# AT1846S.net
KiCad netlist of a schematic drawn in EAGLE
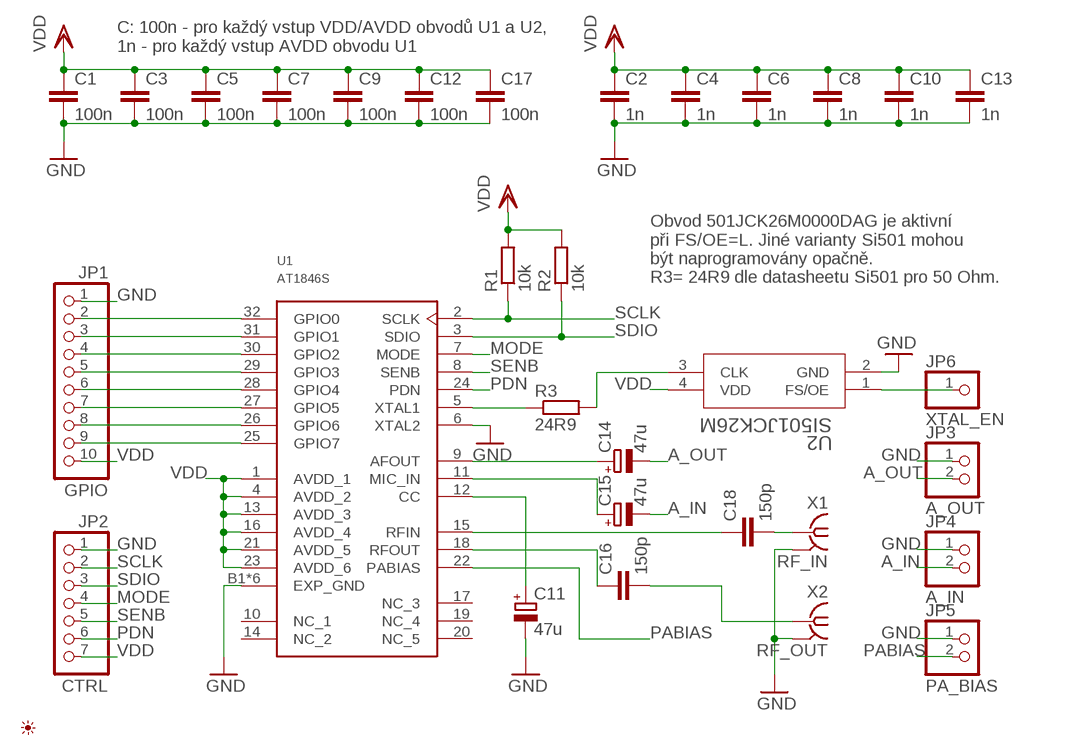
[diagram p0: schematic, sheet 1]

(export (version "E")
  (design (tool "Eeschema 10.0.6"))
  (components
    (comp (ref "C1")
      (value "100n")
      (footprint "eagle-import:C0603")
      (libsource (lib "eagle-import") (part "C-EUC0603"))
    )
    (comp (ref "C2")
      (value "1n")
      (footprint "eagle-import:C0603")
      (libsource (lib "eagle-import") (part "C-EUC0603"))
    )
    (comp (ref "C3")
      (value "100n")
      (footprint "eagle-import:C0603")
      (libsource (lib "eagle-import") (part "C-EUC0603"))
    )
    (comp (ref "C4")
      (value "1n")
      (footprint "eagle-import:C0603")
      (libsource (lib "eagle-import") (part "C-EUC0603"))
    )
    (comp (ref "C5")
      (value "100n")
      (footprint "eagle-import:C0603")
      (libsource (lib "eagle-import") (part "C-EUC0603"))
    )
    (comp (ref "C6")
      (value "1n")
      (footprint "eagle-import:C0603")
      (libsource (lib "eagle-import") (part "C-EUC0603"))
    )
    (comp (ref "C7")
      (value "100n")
      (footprint "eagle-import:C0603")
      (libsource (lib "eagle-import") (part "C-EUC0603"))
    )
    (comp (ref "C8")
      (value "1n")
      (footprint "eagle-import:C0603")
      (libsource (lib "eagle-import") (part "C-EUC0603"))
    )
    (comp (ref "C9")
      (value "100n")
      (footprint "eagle-import:C0603")
      (libsource (lib "eagle-import") (part "C-EUC0603"))
    )
    (comp (ref "C10")
      (value "1n")
      (footprint "eagle-import:C0603")
      (libsource (lib "eagle-import") (part "C-EUC0603"))
    )
    (comp (ref "C11")
      (value "47u")
      (footprint "eagle-import:SMC_A")
      (libsource (lib "eagle-import") (part "CPOL-EUSMCA"))
    )
    (comp (ref "C12")
      (value "100n")
      (footprint "eagle-import:C0603")
      (libsource (lib "eagle-import") (part "C-EUC0603"))
    )
    (comp (ref "C13")
      (value "1n")
      (footprint "eagle-import:C0603")
      (libsource (lib "eagle-import") (part "C-EUC0603"))
    )
    (comp (ref "C14")
      (value "47u")
      (footprint "eagle-import:SMC_A")
      (libsource (lib "eagle-import") (part "CPOL-EUSMCA"))
    )
    (comp (ref "C15")
      (value "47u")
      (footprint "eagle-import:SMC_A")
      (libsource (lib "eagle-import") (part "CPOL-EUSMCA"))
    )
    (comp (ref "C16")
      (value "150p")
      (footprint "eagle-import:C0603")
      (libsource (lib "eagle-import") (part "C-EUC0603"))
    )
    (comp (ref "C17")
      (value "100n")
      (footprint "eagle-import:C0603")
      (libsource (lib "eagle-import") (part "C-EUC0603"))
    )
    (comp (ref "C18")
      (value "150p")
      (footprint "eagle-import:C0603")
      (libsource (lib "eagle-import") (part "C-EUC0603"))
    )
    (comp (ref "JP1")
      (value "GPIO")
      (footprint "eagle-import:1X10")
      (libsource (lib "eagle-import") (part "PINHD-1X10"))
    )
    (comp (ref "JP2")
      (value "CTRL")
      (footprint "eagle-import:1X07")
      (libsource (lib "eagle-import") (part "PINHD-1X7"))
    )
    (comp (ref "JP3")
      (value "A_OUT")
      (footprint "eagle-import:1X02")
      (libsource (lib "eagle-import") (part "PINHD-1X2"))
    )
    (comp (ref "JP4")
      (value "A_IN")
      (footprint "eagle-import:1X02")
      (libsource (lib "eagle-import") (part "PINHD-1X2"))
    )
    (comp (ref "JP5")
      (value "PA_BIAS")
      (footprint "eagle-import:1X02")
      (libsource (lib "eagle-import") (part "PINHD-1X2"))
    )
    (comp (ref "JP6")
      (value "XTAL_EN")
      (footprint "eagle-import:1X01")
      (libsource (lib "eagle-import") (part "PINHD-1X1"))
    )
    (comp (ref "PICTO1")
      (value "PICTO_1")
      (footprint "eagle-import:PICTO_1")
      (libsource (lib "eagle-import") (part "PICTO_1"))
    )
    (comp (ref "R1")
      (value "10k")
      (footprint "eagle-import:R0603")
      (libsource (lib "eagle-import") (part "R-EU_R0603"))
    )
    (comp (ref "R2")
      (value "10k")
      (footprint "eagle-import:R0603")
      (libsource (lib "eagle-import") (part "R-EU_R0603"))
    )
    (comp (ref "R3")
      (value "24R9")
      (footprint "eagle-import:R0603")
      (libsource (lib "eagle-import") (part "R-EU_R0603"))
    )
    (comp (ref "U1")
      (value "AT1846S")
      (footprint "eagle-import:QFN32")
      (libsource (lib "eagle-import") (part "AT1846S"))
    )
    (comp (ref "U2")
      (value "SI501JCK26M")
      (footprint "eagle-import:SI501_4_2X2.5")
      (fields (field (name "MANUFACTURER_PART_NUMBER") "501"))
      (libsource (lib "eagle-import") (part "501"))
    )
    (comp (ref "X1")
      (value "RF_IN")
      (footprint "eagle-import:J502-ND-142-0701-801_806")
      (fields (field (name "MF") "JOHNSON COMPONENTS") (field (name "MPN") "142-0701-801"))
      (libsource (lib "eagle-import") (part "SMA-142-0701-801/806"))
    )
    (comp (ref "X2")
      (value "RF_OUT")
      (footprint "eagle-import:J502-ND-142-0701-801_806")
      (fields (field (name "MF") "JOHNSON COMPONENTS") (field (name "MPN") "142-0701-801"))
      (libsource (lib "eagle-import") (part "SMA-142-0701-801/806"))
    )
  )
  (nets
    (net (code "1") (name "/A_IN") (class "Default")
      (node (ref "C15") (pin "-") (pinfunction "-_-") (pintype "passive"))
      (node (ref "JP4") (pin "2") (pinfunction "2_2") (pintype "passive"))
    )
    (net (code "2") (name "/A_OUT") (class "Default")
      (node (ref "C14") (pin "-") (pinfunction "-_-") (pintype "passive"))
      (node (ref "JP3") (pin "2") (pinfunction "2_2") (pintype "passive"))
    )
    (net (code "3") (name "/MODE") (class "Default")
      (node (ref "JP2") (pin "4") (pinfunction "4_4") (pintype "passive"))
      (node (ref "U1") (pin "7") (pinfunction "MODE_7") (pintype "bidirectional"))
    )
    (net (code "4") (name "/PABIAS") (class "Default")
      (node (ref "JP5") (pin "2") (pinfunction "2_2") (pintype "passive"))
      (node (ref "U1") (pin "22") (pinfunction "PABIAS_22") (pintype "bidirectional"))
    )
    (net (code "5") (name "/PDN") (class "Default")
      (node (ref "JP2") (pin "6") (pinfunction "6_6") (pintype "passive"))
      (node (ref "U1") (pin "24") (pinfunction "PDN_24") (pintype "bidirectional"))
    )
    (net (code "6") (name "/SCLK") (class "Default")
      (node (ref "JP2") (pin "2") (pinfunction "2_2") (pintype "passive"))
      (node (ref "R1") (pin "1") (pinfunction "1_1") (pintype "passive"))
      (node (ref "U1") (pin "2") (pinfunction "SCLK_2") (pintype "input"))
    )
    (net (code "7") (name "/SDIO") (class "Default")
      (node (ref "JP2") (pin "3") (pinfunction "3_3") (pintype "passive"))
      (node (ref "R2") (pin "1") (pinfunction "1_1") (pintype "passive"))
      (node (ref "U1") (pin "3") (pinfunction "SDIO_3") (pintype "bidirectional"))
    )
    (net (code "8") (name "/SENB") (class "Default")
      (node (ref "JP2") (pin "5") (pinfunction "5_5") (pintype "passive"))
      (node (ref "U1") (pin "8") (pinfunction "SENB_8") (pintype "bidirectional"))
    )
    (net (code "9") (name "GND") (class "Default")
      (node (ref "C1") (pin "2") (pinfunction "2_2") (pintype "passive"))
      (node (ref "C10") (pin "2") (pinfunction "2_2") (pintype "passive"))
      (node (ref "C11") (pin "-") (pinfunction "-_-") (pintype "passive"))
      (node (ref "C12") (pin "2") (pinfunction "2_2") (pintype "passive"))
      (node (ref "C13") (pin "2") (pinfunction "2_2") (pintype "passive"))
      (node (ref "C17") (pin "2") (pinfunction "2_2") (pintype "passive"))
      (node (ref "C2") (pin "2") (pinfunction "2_2") (pintype "passive"))
      (node (ref "C3") (pin "2") (pinfunction "2_2") (pintype "passive"))
      (node (ref "C4") (pin "2") (pinfunction "2_2") (pintype "passive"))
      (node (ref "C5") (pin "2") (pinfunction "2_2") (pintype "passive"))
      (node (ref "C6") (pin "2") (pinfunction "2_2") (pintype "passive"))
      (node (ref "C7") (pin "2") (pinfunction "2_2") (pintype "passive"))
      (node (ref "C8") (pin "2") (pinfunction "2_2") (pintype "passive"))
      (node (ref "C9") (pin "2") (pinfunction "2_2") (pintype "passive"))
      (node (ref "JP1") (pin "1") (pinfunction "1_1") (pintype "passive"))
      (node (ref "JP2") (pin "1") (pinfunction "1_1") (pintype "passive"))
      (node (ref "JP3") (pin "1") (pinfunction "1_1") (pintype "passive"))
      (node (ref "JP4") (pin "1") (pinfunction "1_1") (pintype "passive"))
      (node (ref "JP5") (pin "1") (pinfunction "1_1") (pintype "passive"))
      (node (ref "U1") (pin "6") (pinfunction "XTAL2_6") (pintype "bidirectional"))
      (node (ref "U1") (pin "B1") (pinfunction "EXP_GND_B1") (pintype "bidirectional"))
      (node (ref "U1") (pin "B2") (pinfunction "EXP_GND_B2") (pintype "bidirectional"))
      (node (ref "U1") (pin "B3") (pinfunction "EXP_GND_B3") (pintype "bidirectional"))
      (node (ref "U1") (pin "B4") (pinfunction "EXP_GND_B4") (pintype "bidirectional"))
      (node (ref "U1") (pin "B5") (pinfunction "EXP_GND_B5") (pintype "bidirectional"))
      (node (ref "U1") (pin "EXP") (pinfunction "EXP_GND_EXP") (pintype "bidirectional"))
      (node (ref "U2") (pin "2") (pinfunction "GND_2") (pintype "power_in"))
      (node (ref "X1") (pin "G@1") (pinfunction "2_G@1") (pintype "passive"))
      (node (ref "X1") (pin "G@2") (pinfunction "2_G@2") (pintype "passive"))
      (node (ref "X1") (pin "G@3") (pinfunction "2_G@3") (pintype "passive"))
      (node (ref "X1") (pin "G@4") (pinfunction "2_G@4") (pintype "passive"))
      (node (ref "X2") (pin "G@1") (pinfunction "2_G@1") (pintype "passive"))
      (node (ref "X2") (pin "G@2") (pinfunction "2_G@2") (pintype "passive"))
      (node (ref "X2") (pin "G@3") (pinfunction "2_G@3") (pintype "passive"))
      (node (ref "X2") (pin "G@4") (pinfunction "2_G@4") (pintype "passive"))
    )
    (net (code "10") (name "Net-(C16-Pad2)") (class "Default")
      (node (ref "C16") (pin "2") (pinfunction "2_2") (pintype "passive"))
      (node (ref "X2") (pin "1") (pinfunction "1_1") (pintype "passive"))
    )
    (net (code "11") (name "Net-(C18-Pad2)") (class "Default")
      (node (ref "C18") (pin "2") (pinfunction "2_2") (pintype "passive"))
      (node (ref "X1") (pin "1") (pinfunction "1_1") (pintype "passive"))
    )
    (net (code "12") (name "Net-(U1-AFOUT)") (class "Default")
      (node (ref "C14") (pin "+") (pinfunction "+_+") (pintype "passive"))
      (node (ref "U1") (pin "9") (pinfunction "AFOUT_9") (pintype "output"))
    )
    (net (code "13") (name "Net-(U1-CC)") (class "Default")
      (node (ref "C11") (pin "+") (pinfunction "+_+") (pintype "passive"))
      (node (ref "U1") (pin "12") (pinfunction "CC_12") (pintype "bidirectional"))
    )
    (net (code "14") (name "Net-(U1-GPIO0)") (class "Default")
      (node (ref "JP1") (pin "2") (pinfunction "2_2") (pintype "passive"))
      (node (ref "U1") (pin "32") (pinfunction "GPIO0_32") (pintype "bidirectional"))
    )
    (net (code "15") (name "Net-(U1-GPIO1)") (class "Default")
      (node (ref "JP1") (pin "3") (pinfunction "3_3") (pintype "passive"))
      (node (ref "U1") (pin "31") (pinfunction "GPIO1_31") (pintype "bidirectional"))
    )
    (net (code "16") (name "Net-(U1-GPIO2)") (class "Default")
      (node (ref "JP1") (pin "4") (pinfunction "4_4") (pintype "passive"))
      (node (ref "U1") (pin "30") (pinfunction "GPIO2_30") (pintype "bidirectional"))
    )
    (net (code "17") (name "Net-(U1-GPIO3)") (class "Default")
      (node (ref "JP1") (pin "5") (pinfunction "5_5") (pintype "passive"))
      (node (ref "U1") (pin "29") (pinfunction "GPIO3_29") (pintype "bidirectional"))
    )
    (net (code "18") (name "Net-(U1-GPIO4)") (class "Default")
      (node (ref "JP1") (pin "6") (pinfunction "6_6") (pintype "passive"))
      (node (ref "U1") (pin "28") (pinfunction "GPIO4_28") (pintype "bidirectional"))
    )
    (net (code "19") (name "Net-(U1-GPIO5)") (class "Default")
      (node (ref "JP1") (pin "7") (pinfunction "7_7") (pintype "passive"))
      (node (ref "U1") (pin "27") (pinfunction "GPIO5_27") (pintype "bidirectional"))
    )
    (net (code "20") (name "Net-(U1-GPIO6)") (class "Default")
      (node (ref "JP1") (pin "8") (pinfunction "8_8") (pintype "passive"))
      (node (ref "U1") (pin "26") (pinfunction "GPIO6_26") (pintype "bidirectional"))
    )
    (net (code "21") (name "Net-(U1-GPIO7)") (class "Default")
      (node (ref "JP1") (pin "9") (pinfunction "9_9") (pintype "passive"))
      (node (ref "U1") (pin "25") (pinfunction "GPIO7_25") (pintype "bidirectional"))
    )
    (net (code "22") (name "Net-(U1-MIC_IN)") (class "Default")
      (node (ref "C15") (pin "+") (pinfunction "+_+") (pintype "passive"))
      (node (ref "U1") (pin "11") (pinfunction "MIC_IN_11") (pintype "input"))
    )
    (net (code "23") (name "Net-(U1-RFIN)") (class "Default")
      (node (ref "C18") (pin "1") (pinfunction "1_1") (pintype "passive"))
      (node (ref "U1") (pin "15") (pinfunction "RFIN_15") (pintype "input"))
    )
    (net (code "24") (name "Net-(U1-RFOUT)") (class "Default")
      (node (ref "C16") (pin "1") (pinfunction "1_1") (pintype "passive"))
      (node (ref "U1") (pin "18") (pinfunction "RFOUT_18") (pintype "output"))
    )
    (net (code "25") (name "Net-(U1-XTAL1)") (class "Default")
      (node (ref "R3") (pin "1") (pinfunction "1_1") (pintype "passive"))
      (node (ref "U1") (pin "5") (pinfunction "XTAL1_5") (pintype "bidirectional"))
    )
    (net (code "26") (name "Net-(U2-CLK)") (class "Default")
      (node (ref "R3") (pin "2") (pinfunction "2_2") (pintype "passive"))
      (node (ref "U2") (pin "3") (pinfunction "CLK_3") (pintype "output"))
    )
    (net (code "27") (name "Net-(U2-FS{slash}OE)") (class "Default")
      (node (ref "JP6") (pin "1") (pinfunction "1_1") (pintype "passive"))
      (node (ref "U2") (pin "1") (pinfunction "FS/OE_1") (pintype "passive"))
    )
    (net (code "28") (name "VDD") (class "Default")
      (node (ref "C1") (pin "1") (pinfunction "1_1") (pintype "passive"))
      (node (ref "C10") (pin "1") (pinfunction "1_1") (pintype "passive"))
      (node (ref "C12") (pin "1") (pinfunction "1_1") (pintype "passive"))
      (node (ref "C13") (pin "1") (pinfunction "1_1") (pintype "passive"))
      (node (ref "C17") (pin "1") (pinfunction "1_1") (pintype "passive"))
      (node (ref "C2") (pin "1") (pinfunction "1_1") (pintype "passive"))
      (node (ref "C3") (pin "1") (pinfunction "1_1") (pintype "passive"))
      (node (ref "C4") (pin "1") (pinfunction "1_1") (pintype "passive"))
      (node (ref "C5") (pin "1") (pinfunction "1_1") (pintype "passive"))
      (node (ref "C6") (pin "1") (pinfunction "1_1") (pintype "passive"))
      (node (ref "C7") (pin "1") (pinfunction "1_1") (pintype "passive"))
      (node (ref "C8") (pin "1") (pinfunction "1_1") (pintype "passive"))
      (node (ref "C9") (pin "1") (pinfunction "1_1") (pintype "passive"))
      (node (ref "JP1") (pin "10") (pinfunction "10_10") (pintype "passive"))
      (node (ref "JP2") (pin "7") (pinfunction "7_7") (pintype "passive"))
      (node (ref "R1") (pin "2") (pinfunction "2_2") (pintype "passive"))
      (node (ref "R2") (pin "2") (pinfunction "2_2") (pintype "passive"))
      (node (ref "U1") (pin "1") (pinfunction "AVDD_1_1") (pintype "power_in"))
      (node (ref "U1") (pin "13") (pinfunction "AVDD_3_13") (pintype "power_in"))
      (node (ref "U1") (pin "16") (pinfunction "AVDD_4_16") (pintype "power_in"))
      (node (ref "U1") (pin "21") (pinfunction "AVDD_5_21") (pintype "power_in"))
      (node (ref "U1") (pin "23") (pinfunction "AVDD_6_23") (pintype "power_in"))
      (node (ref "U1") (pin "4") (pinfunction "AVDD_2_4") (pintype "power_in"))
      (node (ref "U2") (pin "4") (pinfunction "VDD_4") (pintype "power_in"))
    )
    (net (code "29") (name "unconnected-(U1-NC_1-Pad10)") (class "Default")
      (node (ref "U1") (pin "10") (pinfunction "NC_1_10") (pintype "no_connect"))
    )
    (net (code "30") (name "unconnected-(U1-NC_2-Pad14)") (class "Default")
      (node (ref "U1") (pin "14") (pinfunction "NC_2_14") (pintype "no_connect"))
    )
    (net (code "31") (name "unconnected-(U1-NC_3-Pad17)") (class "Default")
      (node (ref "U1") (pin "17") (pinfunction "NC_3_17") (pintype "no_connect"))
    )
    (net (code "32") (name "unconnected-(U1-NC_4-Pad19)") (class "Default")
      (node (ref "U1") (pin "19") (pinfunction "NC_4_19") (pintype "bidirectional"))
    )
    (net (code "33") (name "unconnected-(U1-NC_5-Pad20)") (class "Default")
      (node (ref "U1") (pin "20") (pinfunction "NC_5_20") (pintype "bidirectional"))
    )
  )
)
